# topsheet_Controller.net
KiCad netlist of a schematic drawn in Altium Designer
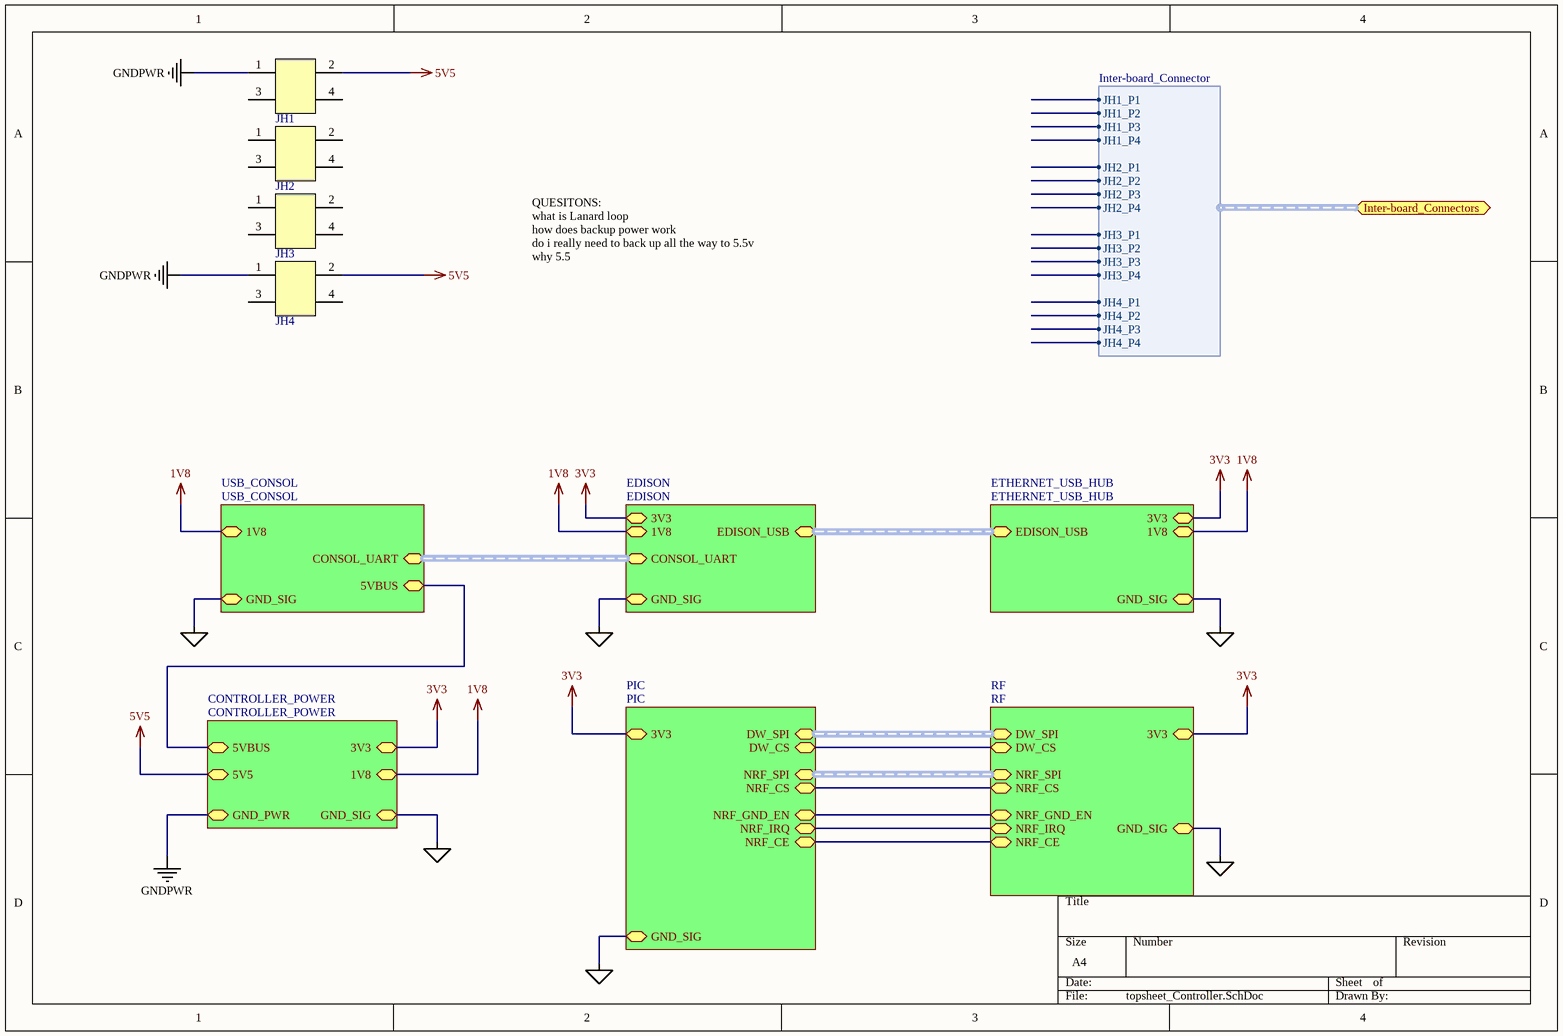
[diagram p0: topsheet_Controller.SchDoc]

(export (version "E")
  (design (tool "Eeschema 10.0.6"))
  (components
    (comp (ref "JH1")
      (value "CONN HEADER 2x2POS T/H")
      (footprint "CONN_2x2_100MIL_MALE_SAMTEC")
      (libsource (lib "SSI") (part "CONN_2x2"))
    )
    (comp (ref "JH2")
      (value "CONN HEADER 2x2POS T/H")
      (footprint "CONN_2x2_100MIL_MALE_SAMTEC")
      (libsource (lib "SSI") (part "CONN_2x2"))
    )
    (comp (ref "JH3")
      (value "CONN HEADER 2x2POS T/H")
      (footprint "CONN_2x2_100MIL_MALE_SAMTEC")
      (libsource (lib "SSI") (part "CONN_2x2"))
    )
    (comp (ref "JH4")
      (value "CONN HEADER 2x2POS T/H")
      (footprint "CONN_2x2_100MIL_MALE_SAMTEC")
      (libsource (lib "SSI") (part "CONN_2x2"))
    )
  )
  (nets
    (net (code "15") (name "5V5") (class "Default")
      (node (ref "JH1") (pin "2") (pinfunction "2_2") (pintype "passive"))
      (node (ref "JH4") (pin "2") (pinfunction "2_2") (pintype "passive"))
    )
    (net (code "17") (name "GNDPWR") (class "Default")
      (node (ref "JH1") (pin "1") (pinfunction "1_1") (pintype "passive"))
      (node (ref "JH4") (pin "1") (pinfunction "1_1") (pintype "passive"))
    )
    (net (code "18") (name "unconnected-(JH1-Pad3)") (class "Default")
      (node (ref "JH1") (pin "3") (pinfunction "3_3") (pintype "passive"))
    )
    (net (code "19") (name "unconnected-(JH1-Pad4)") (class "Default")
      (node (ref "JH1") (pin "4") (pinfunction "4_4") (pintype "passive"))
    )
    (net (code "20") (name "unconnected-(JH2-Pad1)") (class "Default")
      (node (ref "JH2") (pin "1") (pinfunction "1_1") (pintype "passive"))
    )
    (net (code "21") (name "unconnected-(JH2-Pad2)") (class "Default")
      (node (ref "JH2") (pin "2") (pinfunction "2_2") (pintype "passive"))
    )
    (net (code "22") (name "unconnected-(JH2-Pad3)") (class "Default")
      (node (ref "JH2") (pin "3") (pinfunction "3_3") (pintype "passive"))
    )
    (net (code "23") (name "unconnected-(JH2-Pad4)") (class "Default")
      (node (ref "JH2") (pin "4") (pinfunction "4_4") (pintype "passive"))
    )
    (net (code "24") (name "unconnected-(JH3-Pad1)") (class "Default")
      (node (ref "JH3") (pin "1") (pinfunction "1_1") (pintype "passive"))
    )
    (net (code "25") (name "unconnected-(JH3-Pad2)") (class "Default")
      (node (ref "JH3") (pin "2") (pinfunction "2_2") (pintype "passive"))
    )
    (net (code "26") (name "unconnected-(JH3-Pad3)") (class "Default")
      (node (ref "JH3") (pin "3") (pinfunction "3_3") (pintype "passive"))
    )
    (net (code "27") (name "unconnected-(JH3-Pad4)") (class "Default")
      (node (ref "JH3") (pin "4") (pinfunction "4_4") (pintype "passive"))
    )
    (net (code "28") (name "unconnected-(JH4-Pad3)") (class "Default")
      (node (ref "JH4") (pin "3") (pinfunction "3_3") (pintype "passive"))
    )
    (net (code "29") (name "unconnected-(JH4-Pad4)") (class "Default")
      (node (ref "JH4") (pin "4") (pinfunction "4_4") (pintype "passive"))
    )
  )
)
